# LPDDR4_4X.net
KiCad netlist of a schematic drawn in Altium Designer
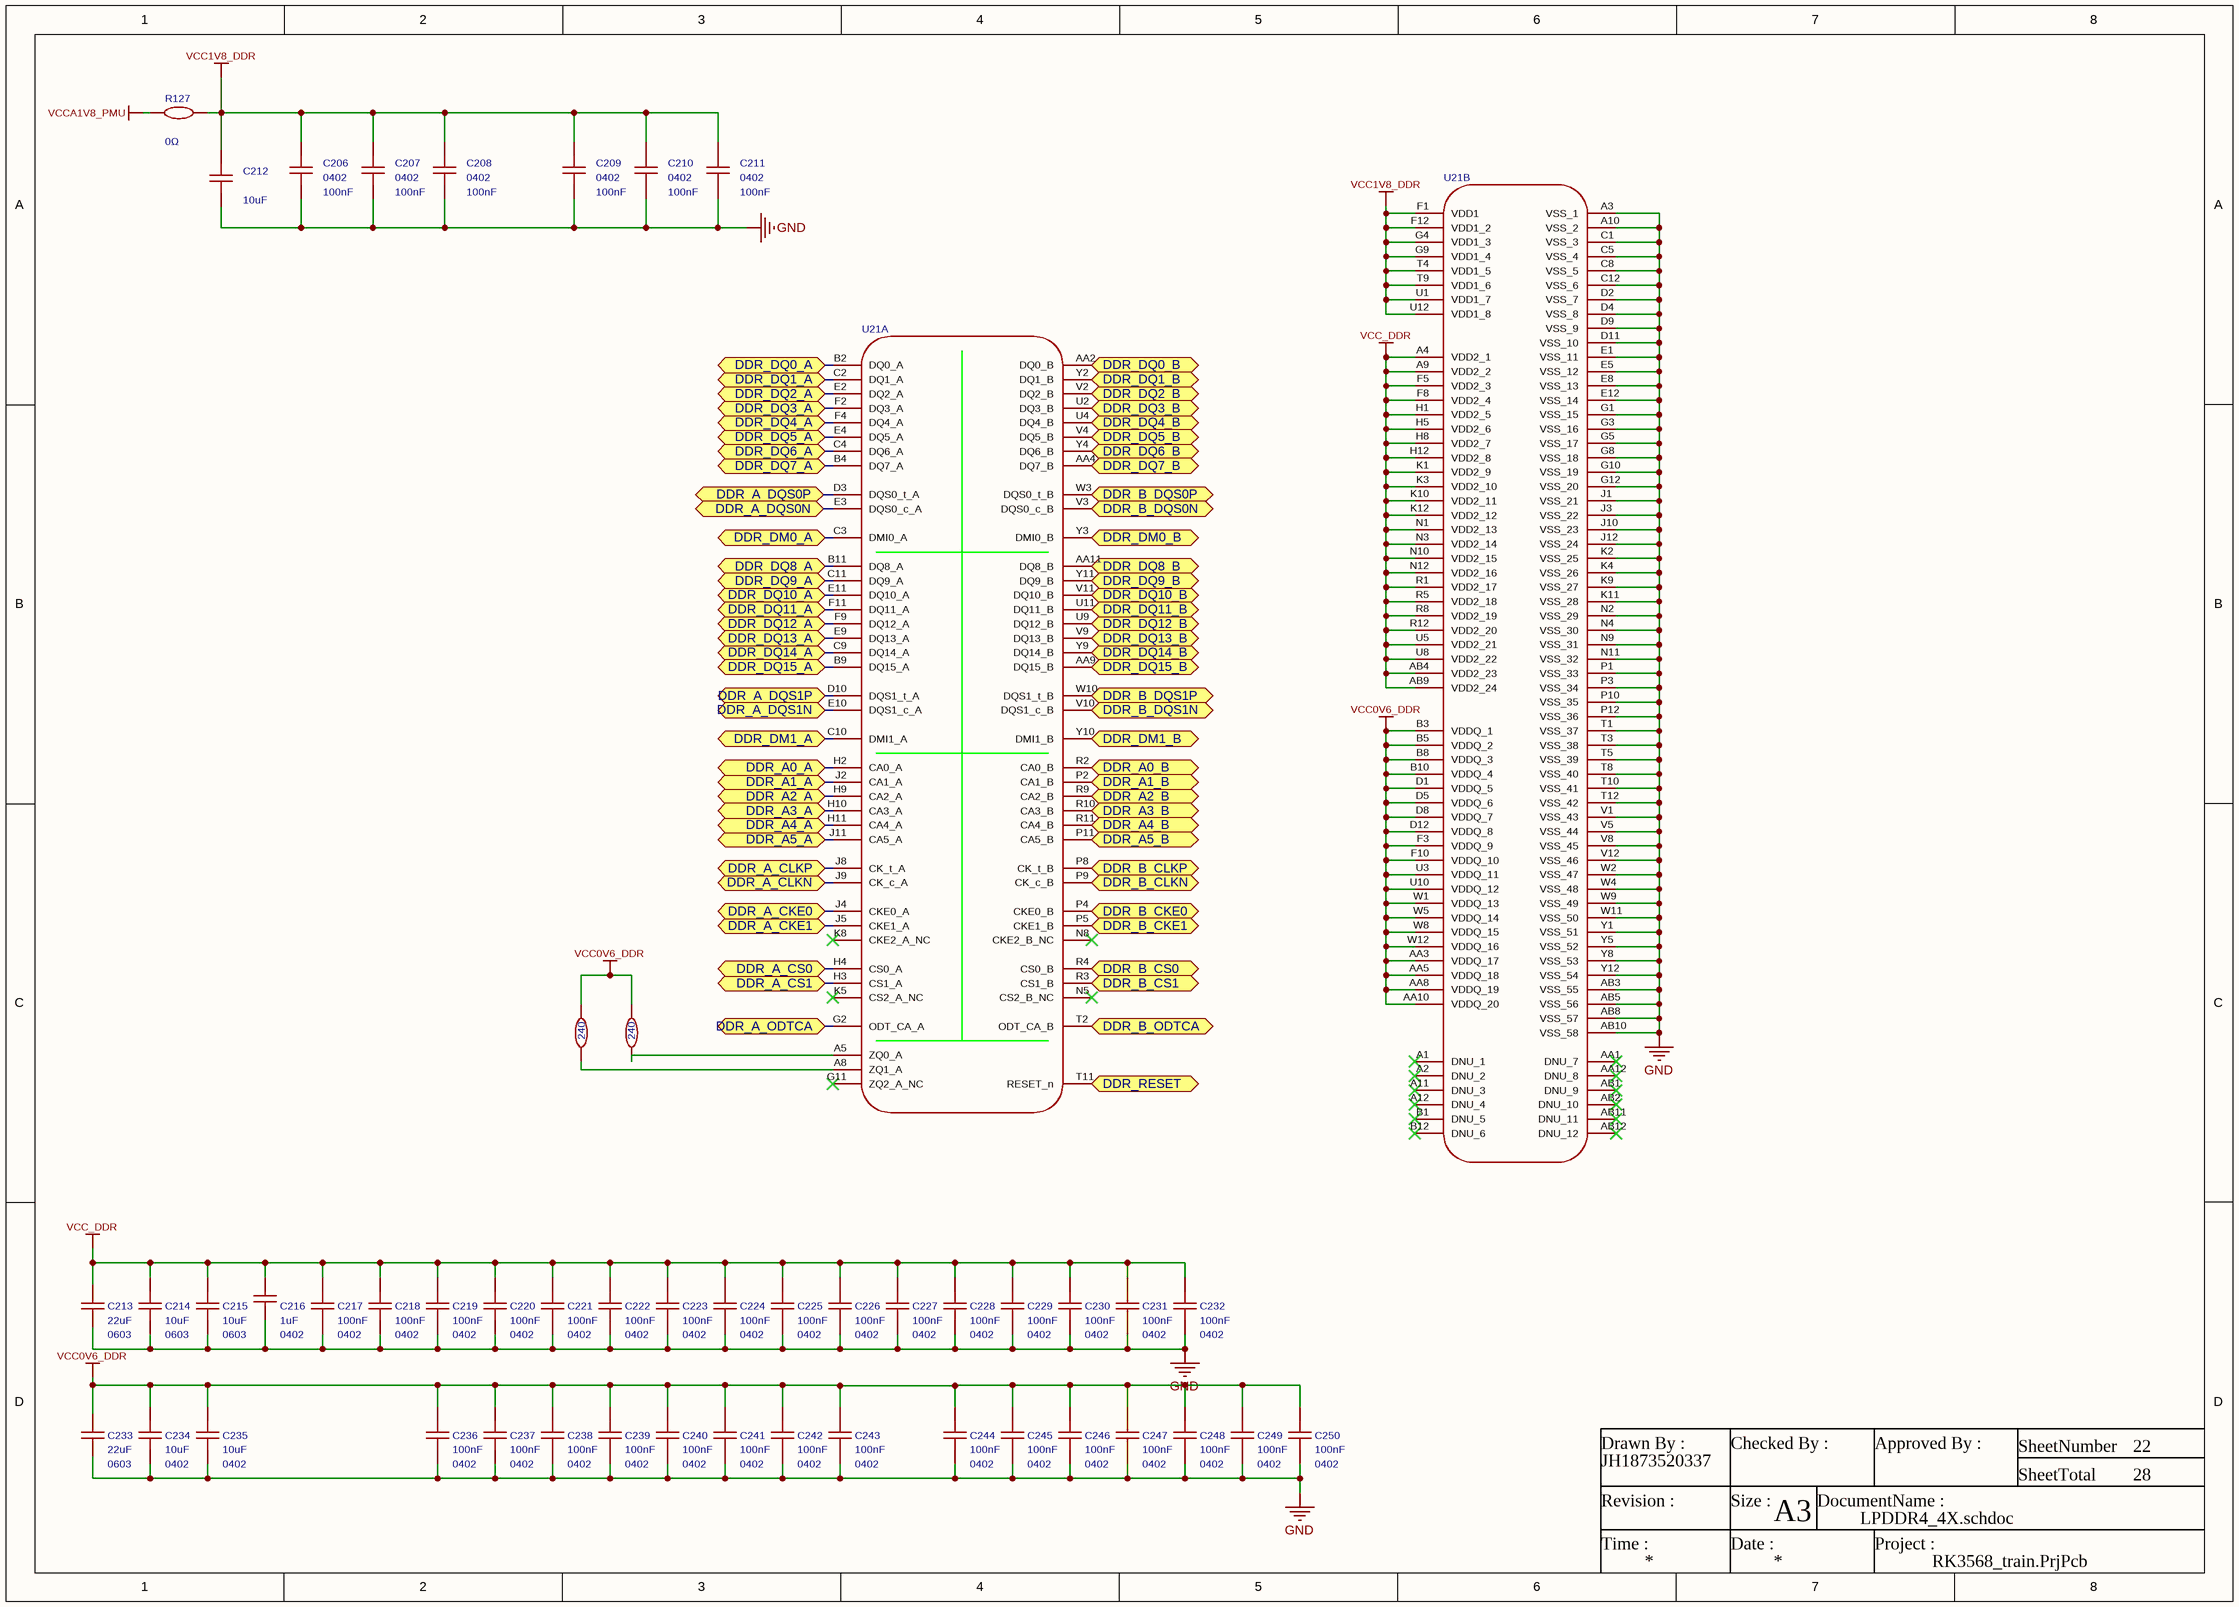
[diagram p0: LPDDR4_4X.schdoc]

(export (version "E")
  (design (tool "Eeschema 10.0.6"))
  (components
    (comp (ref "C206")
      (value "100nF")
      (footprint "MYC0402")
      (description "容值:100nF;精度:±10%;额定电压:50V;材质(温度系数):X7R;")
      (fields
        (field (name "SUPPLIER FOOTPRINT") "0402")
        (field (name "MANUFACTURER") "SAMSUNG(三星)")
        (field (name "MANUFACTURERPART") "CL05B104KB54PNC")
      )
      (libsource (lib "altium-import") (part "root_0_CL05B104KB54PNC_"))
    )
    (comp (ref "C207")
      (value "100nF")
      (footprint "MYC0402")
      (description "容值:100nF;精度:±10%;额定电压:50V;材质(温度系数):X7R;")
      (fields
        (field (name "SUPPLIER FOOTPRINT") "0402")
        (field (name "MANUFACTURER") "SAMSUNG(三星)")
        (field (name "MANUFACTURERPART") "CL05B104KB54PNC")
      )
      (libsource (lib "altium-import") (part "root_0_CL05B104KB54PNC_"))
    )
    (comp (ref "C208")
      (value "100nF")
      (footprint "MYC0402")
      (description "容值:100nF;精度:±10%;额定电压:50V;材质(温度系数):X7R;")
      (fields
        (field (name "SUPPLIER FOOTPRINT") "0402")
        (field (name "MANUFACTURER") "SAMSUNG(三星)")
        (field (name "MANUFACTURERPART") "CL05B104KB54PNC")
      )
      (libsource (lib "altium-import") (part "root_0_CL05B104KB54PNC_"))
    )
    (comp (ref "C209")
      (value "100nF")
      (footprint "MYC0402")
      (description "容值:100nF;精度:±10%;额定电压:50V;材质(温度系数):X7R;")
      (fields
        (field (name "SUPPLIER FOOTPRINT") "0402")
        (field (name "MANUFACTURER") "SAMSUNG(三星)")
        (field (name "MANUFACTURERPART") "CL05B104KB54PNC")
      )
      (libsource (lib "altium-import") (part "root_0_CL05B104KB54PNC_"))
    )
    (comp (ref "C210")
      (value "100nF")
      (footprint "MYC0402")
      (description "容值:100nF;精度:±10%;额定电压:50V;材质(温度系数):X7R;")
      (fields
        (field (name "SUPPLIER FOOTPRINT") "0402")
        (field (name "MANUFACTURER") "SAMSUNG(三星)")
        (field (name "MANUFACTURERPART") "CL05B104KB54PNC")
      )
      (libsource (lib "altium-import") (part "root_0_CL05B104KB54PNC_"))
    )
    (comp (ref "C211")
      (value "100nF")
      (footprint "MYC0402")
      (description "容值:100nF;精度:±10%;额定电压:50V;材质(温度系数):X7R;")
      (fields
        (field (name "SUPPLIER FOOTPRINT") "0402")
        (field (name "MANUFACTURER") "SAMSUNG(三星)")
        (field (name "MANUFACTURERPART") "CL05B104KB54PNC")
      )
      (libsource (lib "altium-import") (part "root_0_CL05B104KB54PNC_"))
    )
    (comp (ref "C212")
      (value "10uF")
      (footprint "C0603")
      (description "容值:10uF;精度:±10%;额定电压:10V;材质(温度系数):X5R;")
      (fields (field (name "MANUFACTURER") "SAMSUNG(三星)") (field (name "MANUFACTURERPART") "CL10A106KP8NNNC"))
      (libsource (lib "altium-import") (part "root_1_CL10A106KP8NNNC_"))
    )
    (comp (ref "C213")
      (value "22uF")
      (footprint "C0603")
      (description "容值:22uF;精度:±20%;额定电压:6.3V;材质(温度系数):X5R;")
      (fields
        (field (name "SUPPLIER FOOTPRINT") "0603")
        (field (name "MANUFACTURER") "SAMSUNG(三星)")
        (field (name "MANUFACTURERPART") "CL10A226MQ8NRNC")
      )
      (libsource (lib "altium-import") (part "root_1_CL10A226MQ8NRNC_"))
    )
    (comp (ref "C214")
      (value "10uF")
      (footprint "C0603")
      (description "容值:10uF;精度:±10%;额定电压:10V;材质(温度系数):X5R;")
      (fields
        (field (name "SUPPLIER FOOTPRINT") "0603")
        (field (name "MANUFACTURER") "SAMSUNG(三星)")
        (field (name "MANUFACTURERPART") "CL10A106KP8NNNC")
      )
      (libsource (lib "altium-import") (part "root_1_CL10A106KP8NNNC_"))
    )
    (comp (ref "C215")
      (value "10uF")
      (footprint "C0603")
      (description "容值:10uF;精度:±10%;额定电压:10V;材质(温度系数):X5R;")
      (fields
        (field (name "SUPPLIER FOOTPRINT") "0603")
        (field (name "MANUFACTURER") "SAMSUNG(三星)")
        (field (name "MANUFACTURERPART") "CL10A106KP8NNNC")
      )
      (libsource (lib "altium-import") (part "root_1_CL10A106KP8NNNC_"))
    )
    (comp (ref "C216")
      (value "1uF")
      (footprint "MYC0402")
      (description "容值:1uF;精度:±10%;额定电压:10V;材质(温度系数):X5R;")
      (fields
        (field (name "SUPPLIER FOOTPRINT") "0402")
        (field (name "MANUFACTURER") "SAMSUNG(三星)")
        (field (name "MANUFACTURERPART") "CL05A105KP5NNNC")
      )
      (libsource (lib "altium-import") (part "root_1_CL05A105KP5NNNC_"))
    )
    (comp (ref "C217")
      (value "100nF")
      (footprint "MYC0402")
      (description "容值:100nF;精度:±10%;额定电压:50V;材质(温度系数):X7R;")
      (fields
        (field (name "SUPPLIER FOOTPRINT") "0402")
        (field (name "MANUFACTURER") "SAMSUNG(三星)")
        (field (name "MANUFACTURERPART") "CL05B104KB54PNC")
      )
      (libsource (lib "altium-import") (part "root_2_CL05B104KB54PNC_"))
    )
    (comp (ref "C218")
      (value "100nF")
      (footprint "MYC0402")
      (description "容值:100nF;精度:±10%;额定电压:50V;材质(温度系数):X7R;")
      (fields
        (field (name "SUPPLIER FOOTPRINT") "0402")
        (field (name "MANUFACTURER") "SAMSUNG(三星)")
        (field (name "MANUFACTURERPART") "CL05B104KB54PNC")
      )
      (libsource (lib "altium-import") (part "root_2_CL05B104KB54PNC_"))
    )
    (comp (ref "C219")
      (value "100nF")
      (footprint "MYC0402")
      (description "容值:100nF;精度:±10%;额定电压:50V;材质(温度系数):X7R;")
      (fields
        (field (name "SUPPLIER FOOTPRINT") "0402")
        (field (name "MANUFACTURER") "SAMSUNG(三星)")
        (field (name "MANUFACTURERPART") "CL05B104KB54PNC")
      )
      (libsource (lib "altium-import") (part "root_2_CL05B104KB54PNC_"))
    )
    (comp (ref "C220")
      (value "100nF")
      (footprint "MYC0402")
      (description "容值:100nF;精度:±10%;额定电压:50V;材质(温度系数):X7R;")
      (fields
        (field (name "SUPPLIER FOOTPRINT") "0402")
        (field (name "MANUFACTURER") "SAMSUNG(三星)")
        (field (name "MANUFACTURERPART") "CL05B104KB54PNC")
      )
      (libsource (lib "altium-import") (part "root_2_CL05B104KB54PNC_"))
    )
    (comp (ref "C221")
      (value "100nF")
      (footprint "MYC0402")
      (description "容值:100nF;精度:±10%;额定电压:50V;材质(温度系数):X7R;")
      (fields
        (field (name "SUPPLIER FOOTPRINT") "0402")
        (field (name "MANUFACTURER") "SAMSUNG(三星)")
        (field (name "MANUFACTURERPART") "CL05B104KB54PNC")
      )
      (libsource (lib "altium-import") (part "root_2_CL05B104KB54PNC_"))
    )
    (comp (ref "C222")
      (value "100nF")
      (footprint "MYC0402")
      (description "容值:100nF;精度:±10%;额定电压:50V;材质(温度系数):X7R;")
      (fields
        (field (name "SUPPLIER FOOTPRINT") "0402")
        (field (name "MANUFACTURER") "SAMSUNG(三星)")
        (field (name "MANUFACTURERPART") "CL05B104KB54PNC")
      )
      (libsource (lib "altium-import") (part "root_2_CL05B104KB54PNC_"))
    )
    (comp (ref "C223")
      (value "100nF")
      (footprint "MYC0402")
      (description "容值:100nF;精度:±10%;额定电压:50V;材质(温度系数):X7R;")
      (fields
        (field (name "SUPPLIER FOOTPRINT") "0402")
        (field (name "MANUFACTURER") "SAMSUNG(三星)")
        (field (name "MANUFACTURERPART") "CL05B104KB54PNC")
      )
      (libsource (lib "altium-import") (part "root_2_CL05B104KB54PNC_"))
    )
    (comp (ref "C224")
      (value "100nF")
      (footprint "MYC0402")
      (description "容值:100nF;精度:±10%;额定电压:50V;材质(温度系数):X7R;")
      (fields
        (field (name "SUPPLIER FOOTPRINT") "0402")
        (field (name "MANUFACTURER") "SAMSUNG(三星)")
        (field (name "MANUFACTURERPART") "CL05B104KB54PNC")
      )
      (libsource (lib "altium-import") (part "root_2_CL05B104KB54PNC_"))
    )
    (comp (ref "C225")
      (value "100nF")
      (footprint "MYC0402")
      (description "容值:100nF;精度:±10%;额定电压:50V;材质(温度系数):X7R;")
      (fields
        (field (name "SUPPLIER FOOTPRINT") "0402")
        (field (name "MANUFACTURER") "SAMSUNG(三星)")
        (field (name "MANUFACTURERPART") "CL05B104KB54PNC")
      )
      (libsource (lib "altium-import") (part "root_2_CL05B104KB54PNC_"))
    )
    (comp (ref "C226")
      (value "100nF")
      (footprint "MYC0402")
      (description "容值:100nF;精度:±10%;额定电压:50V;材质(温度系数):X7R;")
      (fields
        (field (name "SUPPLIER FOOTPRINT") "0402")
        (field (name "MANUFACTURER") "SAMSUNG(三星)")
        (field (name "MANUFACTURERPART") "CL05B104KB54PNC")
      )
      (libsource (lib "altium-import") (part "root_2_CL05B104KB54PNC_"))
    )
    (comp (ref "C227")
      (value "100nF")
      (footprint "MYC0402")
      (description "容值:100nF;精度:±10%;额定电压:50V;材质(温度系数):X7R;")
      (fields
        (field (name "SUPPLIER FOOTPRINT") "0402")
        (field (name "MANUFACTURER") "SAMSUNG(三星)")
        (field (name "MANUFACTURERPART") "CL05B104KB54PNC")
      )
      (libsource (lib "altium-import") (part "root_2_CL05B104KB54PNC_"))
    )
    (comp (ref "C228")
      (value "100nF")
      (footprint "MYC0402")
      (description "容值:100nF;精度:±10%;额定电压:50V;材质(温度系数):X7R;")
      (fields
        (field (name "SUPPLIER FOOTPRINT") "0402")
        (field (name "MANUFACTURER") "SAMSUNG(三星)")
        (field (name "MANUFACTURERPART") "CL05B104KB54PNC")
      )
      (libsource (lib "altium-import") (part "root_2_CL05B104KB54PNC_"))
    )
    (comp (ref "C229")
      (value "100nF")
      (footprint "MYC0402")
      (description "容值:100nF;精度:±10%;额定电压:50V;材质(温度系数):X7R;")
      (fields
        (field (name "SUPPLIER FOOTPRINT") "0402")
        (field (name "MANUFACTURER") "SAMSUNG(三星)")
        (field (name "MANUFACTURERPART") "CL05B104KB54PNC")
      )
      (libsource (lib "altium-import") (part "root_2_CL05B104KB54PNC_"))
    )
    (comp (ref "C230")
      (value "100nF")
      (footprint "MYC0402")
      (description "容值:100nF;精度:±10%;额定电压:50V;材质(温度系数):X7R;")
      (fields
        (field (name "SUPPLIER FOOTPRINT") "0402")
        (field (name "MANUFACTURER") "SAMSUNG(三星)")
        (field (name "MANUFACTURERPART") "CL05B104KB54PNC")
      )
      (libsource (lib "altium-import") (part "root_2_CL05B104KB54PNC_"))
    )
    (comp (ref "C231")
      (value "100nF")
      (footprint "MYC0402")
      (description "容值:100nF;精度:±10%;额定电压:50V;材质(温度系数):X7R;")
      (fields
        (field (name "SUPPLIER FOOTPRINT") "0402")
        (field (name "MANUFACTURER") "SAMSUNG(三星)")
        (field (name "MANUFACTURERPART") "CL05B104KB54PNC")
      )
      (libsource (lib "altium-import") (part "root_2_CL05B104KB54PNC_"))
    )
    (comp (ref "C232")
      (value "100nF")
      (footprint "MYC0402")
      (description "容值:100nF;精度:±10%;额定电压:50V;材质(温度系数):X7R;")
      (fields
        (field (name "SUPPLIER FOOTPRINT") "0402")
        (field (name "MANUFACTURER") "SAMSUNG(三星)")
        (field (name "MANUFACTURERPART") "CL05B104KB54PNC")
      )
      (libsource (lib "altium-import") (part "root_2_CL05B104KB54PNC_"))
    )
    (comp (ref "C233")
      (value "22uF")
      (footprint "C0603")
      (description "容值:22uF;精度:±20%;额定电压:6.3V;材质(温度系数):X5R;")
      (fields
        (field (name "SUPPLIER FOOTPRINT") "0603")
        (field (name "MANUFACTURER") "SAMSUNG(三星)")
        (field (name "MANUFACTURERPART") "CL10A226MQ8NRNC")
      )
      (libsource (lib "altium-import") (part "root_1_CL10A226MQ8NRNC_"))
    )
    (comp (ref "C234")
      (value "10uF")
      (footprint "MYC0402")
      (description "容值:10uF;精度:±20%;额定电压:6.3V;材质(温度系数):X5R;")
      (fields
        (field (name "SUPPLIER FOOTPRINT") "0402")
        (field (name "MANUFACTURER") "SAMSUNG(三星)")
        (field (name "MANUFACTURERPART") "CL05A106MQ5NUNC")
      )
      (libsource (lib "altium-import") (part "root_1_CL05A106MQ5NUNC_"))
    )
    (comp (ref "C235")
      (value "10uF")
      (footprint "MYC0402")
      (description "容值:10uF;精度:±20%;额定电压:6.3V;材质(温度系数):X5R;")
      (fields
        (field (name "SUPPLIER FOOTPRINT") "0402")
        (field (name "MANUFACTURER") "SAMSUNG(三星)")
        (field (name "MANUFACTURERPART") "CL05A106MQ5NUNC")
      )
      (libsource (lib "altium-import") (part "root_1_CL05A106MQ5NUNC_"))
    )
    (comp (ref "C236")
      (value "100nF")
      (footprint "MYC0402")
      (description "容值:100nF;精度:±10%;额定电压:50V;材质(温度系数):X7R;")
      (fields
        (field (name "SUPPLIER FOOTPRINT") "0402")
        (field (name "MANUFACTURER") "SAMSUNG(三星)")
        (field (name "MANUFACTURERPART") "CL05B104KB54PNC")
      )
      (libsource (lib "altium-import") (part "root_2_CL05B104KB54PNC_"))
    )
    (comp (ref "C237")
      (value "100nF")
      (footprint "MYC0402")
      (description "容值:100nF;精度:±10%;额定电压:50V;材质(温度系数):X7R;")
      (fields
        (field (name "SUPPLIER FOOTPRINT") "0402")
        (field (name "MANUFACTURER") "SAMSUNG(三星)")
        (field (name "MANUFACTURERPART") "CL05B104KB54PNC")
      )
      (libsource (lib "altium-import") (part "root_2_CL05B104KB54PNC_"))
    )
    (comp (ref "C238")
      (value "100nF")
      (footprint "MYC0402")
      (description "容值:100nF;精度:±10%;额定电压:50V;材质(温度系数):X7R;")
      (fields
        (field (name "SUPPLIER FOOTPRINT") "0402")
        (field (name "MANUFACTURER") "SAMSUNG(三星)")
        (field (name "MANUFACTURERPART") "CL05B104KB54PNC")
      )
      (libsource (lib "altium-import") (part "root_2_CL05B104KB54PNC_"))
    )
    (comp (ref "C239")
      (value "100nF")
      (footprint "MYC0402")
      (description "容值:100nF;精度:±10%;额定电压:50V;材质(温度系数):X7R;")
      (fields
        (field (name "SUPPLIER FOOTPRINT") "0402")
        (field (name "MANUFACTURER") "SAMSUNG(三星)")
        (field (name "MANUFACTURERPART") "CL05B104KB54PNC")
      )
      (libsource (lib "altium-import") (part "root_2_CL05B104KB54PNC_"))
    )
    (comp (ref "C240")
      (value "100nF")
      (footprint "MYC0402")
      (description "容值:100nF;精度:±10%;额定电压:50V;材质(温度系数):X7R;")
      (fields
        (field (name "SUPPLIER FOOTPRINT") "0402")
        (field (name "MANUFACTURER") "SAMSUNG(三星)")
        (field (name "MANUFACTURERPART") "CL05B104KB54PNC")
      )
      (libsource (lib "altium-import") (part "root_2_CL05B104KB54PNC_"))
    )
    (comp (ref "C241")
      (value "100nF")
      (footprint "MYC0402")
      (description "容值:100nF;精度:±10%;额定电压:50V;材质(温度系数):X7R;")
      (fields
        (field (name "SUPPLIER FOOTPRINT") "0402")
        (field (name "MANUFACTURER") "SAMSUNG(三星)")
        (field (name "MANUFACTURERPART") "CL05B104KB54PNC")
      )
      (libsource (lib "altium-import") (part "root_2_CL05B104KB54PNC_"))
    )
    (comp (ref "C242")
      (value "100nF")
      (footprint "MYC0402")
      (description "容值:100nF;精度:±10%;额定电压:50V;材质(温度系数):X7R;")
      (fields
        (field (name "SUPPLIER FOOTPRINT") "0402")
        (field (name "MANUFACTURER") "SAMSUNG(三星)")
        (field (name "MANUFACTURERPART") "CL05B104KB54PNC")
      )
      (libsource (lib "altium-import") (part "root_2_CL05B104KB54PNC_"))
    )
    (comp (ref "C243")
      (value "100nF")
      (footprint "MYC0402")
      (description "容值:100nF;精度:±10%;额定电压:50V;材质(温度系数):X7R;")
      (fields
        (field (name "SUPPLIER FOOTPRINT") "0402")
        (field (name "MANUFACTURER") "SAMSUNG(三星)")
        (field (name "MANUFACTURERPART") "CL05B104KB54PNC")
      )
      (libsource (lib "altium-import") (part "root_2_CL05B104KB54PNC_"))
    )
    (comp (ref "C244")
      (value "100nF")
      (footprint "MYC0402")
      (description "容值:100nF;精度:±10%;额定电压:50V;材质(温度系数):X7R;")
      (fields
        (field (name "SUPPLIER FOOTPRINT") "0402")
        (field (name "MANUFACTURER") "SAMSUNG(三星)")
        (field (name "MANUFACTURERPART") "CL05B104KB54PNC")
      )
      (libsource (lib "altium-import") (part "root_2_CL05B104KB54PNC_"))
    )
    (comp (ref "C245")
      (value "100nF")
      (footprint "MYC0402")
      (description "容值:100nF;精度:±10%;额定电压:50V;材质(温度系数):X7R;")
      (fields
        (field (name "SUPPLIER FOOTPRINT") "0402")
        (field (name "MANUFACTURER") "SAMSUNG(三星)")
        (field (name "MANUFACTURERPART") "CL05B104KB54PNC")
      )
      (libsource (lib "altium-import") (part "root_2_CL05B104KB54PNC_"))
    )
    (comp (ref "C246")
      (value "100nF")
      (footprint "MYC0402")
      (description "容值:100nF;精度:±10%;额定电压:50V;材质(温度系数):X7R;")
      (fields
        (field (name "SUPPLIER FOOTPRINT") "0402")
        (field (name "MANUFACTURER") "SAMSUNG(三星)")
        (field (name "MANUFACTURERPART") "CL05B104KB54PNC")
      )
      (libsource (lib "altium-import") (part "root_2_CL05B104KB54PNC_"))
    )
    (comp (ref "C247")
      (value "100nF")
      (footprint "MYC0402")
      (description "容值:100nF;精度:±10%;额定电压:50V;材质(温度系数):X7R;")
      (fields
        (field (name "SUPPLIER FOOTPRINT") "0402")
        (field (name "MANUFACTURER") "SAMSUNG(三星)")
        (field (name "MANUFACTURERPART") "CL05B104KB54PNC")
      )
      (libsource (lib "altium-import") (part "root_2_CL05B104KB54PNC_"))
    )
    (comp (ref "C248")
      (value "100nF")
      (footprint "MYC0402")
      (description "容值:100nF;精度:±10%;额定电压:50V;材质(温度系数):X7R;")
      (fields
        (field (name "SUPPLIER FOOTPRINT") "0402")
        (field (name "MANUFACTURER") "SAMSUNG(三星)")
        (field (name "MANUFACTURERPART") "CL05B104KB54PNC")
      )
      (libsource (lib "altium-import") (part "root_2_CL05B104KB54PNC_"))
    )
    (comp (ref "C249")
      (value "100nF")
      (footprint "MYC0402")
      (description "容值:100nF;精度:±10%;额定电压:50V;材质(温度系数):X7R;")
      (fields
        (field (name "SUPPLIER FOOTPRINT") "0402")
        (field (name "MANUFACTURER") "SAMSUNG(三星)")
        (field (name "MANUFACTURERPART") "CL05B104KB54PNC")
      )
      (libsource (lib "altium-import") (part "root_2_CL05B104KB54PNC_"))
    )
    (comp (ref "C250")
      (value "100nF")
      (footprint "MYC0402")
      (description "容值:100nF;精度:±10%;额定电压:50V;材质(温度系数):X7R;")
      (fields
        (field (name "SUPPLIER FOOTPRINT") "0402")
        (field (name "MANUFACTURER") "SAMSUNG(三星)")
        (field (name "MANUFACTURERPART") "CL05B104KB54PNC")
      )
      (libsource (lib "altium-import") (part "root_2_CL05B104KB54PNC_"))
    )
    (comp (ref "R127")
      (value "0Ω")
      (footprint "R0603")
      (description "电阻类型:厚膜电阻;阻值:0Ω;精度:±1%;功率:100mW;最大工作电压:75V;工作温度范围:-55℃~+155℃;")
      (fields
        (field (name "MANUFACTURER") "UNI-ROYAL(厚声)")
        (field (name "MANUFACTURERPART") "0603WAF0000T5E")
      )
      (libsource (lib "altium-import") (part "root_2_0603WAF0000T5E_"))
    )
    (comp (ref "R128")
      (value "240")
      (footprint "r0402-nsk")
      (fields (field (name "Comment") "Res_0402"))
      (libsource (lib "altium-import") (part "root_1_Res_0402_"))
    )
    (comp (ref "R129")
      (value "240")
      (footprint "r0402-nsk")
      (fields (field (name "Comment") "Res_0402"))
      (libsource (lib "altium-import") (part "root_1_Res_0402_"))
    )
    (comp (ref "U21")
      (value "LPDDR4")
      (footprint "LPDDR4_MrX")
      (libsource (lib "altium-import") (part "root_0_LPDDR4_"))
    )
  )
  (nets
    (net (code "1") (name "/DDR_A0_A") (class "Default")
      (node (ref "U21") (pin "H2") (pinfunction "CA0_A_H2") (pintype "passive"))
    )
    (net (code "2") (name "/DDR_A0_B") (class "Default")
      (node (ref "U21") (pin "R2") (pinfunction "CA0_B_R2") (pintype "passive"))
    )
    (net (code "3") (name "/DDR_A1_A") (class "Default")
      (node (ref "U21") (pin "J2") (pinfunction "CA1_A_J2") (pintype "passive"))
    )
    (net (code "4") (name "/DDR_A1_B") (class "Default")
      (node (ref "U21") (pin "P2") (pinfunction "CA1_B_P2") (pintype "passive"))
    )
    (net (code "5") (name "/DDR_A2_A") (class "Default")
      (node (ref "U21") (pin "H9") (pinfunction "CA2_A_H9") (pintype "passive"))
    )
    (net (code "6") (name "/DDR_A2_B") (class "Default")
      (node (ref "U21") (pin "R9") (pinfunction "CA2_B_R9") (pintype "passive"))
    )
    (net (code "7") (name "/DDR_A3_A") (class "Default")
      (node (ref "U21") (pin "H10") (pinfunction "CA3_A_H10") (pintype "passive"))
    )
    (net (code "8") (name "/DDR_A3_B") (class "Default")
      (node (ref "U21") (pin "R10") (pinfunction "CA3_B_R10") (pintype "passive"))
    )
    (net (code "9") (name "/DDR_A4_A") (class "Default")
      (node (ref "U21") (pin "H11") (pinfunction "CA4_A_H11") (pintype "passive"))
    )
    (net (code "10") (name "/DDR_A4_B") (class "Default")
      (node (ref "U21") (pin "R11") (pinfunction "CA4_B_R11") (pintype "passive"))
    )
    (net (code "11") (name "/DDR_A5_A") (class "Default")
      (node (ref "U21") (pin "J11") (pinfunction "CA5_A_J11") (pintype "passive"))
    )
    (net (code "12") (name "/DDR_A5_B") (class "Default")
      (node (ref "U21") (pin "P11") (pinfunction "CA5_B_P11") (pintype "passive"))
    )
    (net (code "13") (name "/DDR_A_CKE0") (class "Default")
      (node (ref "U21") (pin "J4") (pinfunction "CKE0_A_J4") (pintype "passive"))
    )
    (net (code "14") (name "/DDR_A_CKE1") (class "Default")
      (node (ref "U21") (pin "J5") (pinfunction "CKE1_A_J5") (pintype "passive"))
    )
    (net (code "15") (name "/DDR_A_CLKN") (class "Default")
      (node (ref "U21") (pin "J9") (pinfunction "CK_c_A_J9") (pintype "passive"))
    )
    (net (code "16") (name "/DDR_A_CLKP") (class "Default")
      (node (ref "U21") (pin "J8") (pinfunction "CK_t_A_J8") (pintype "passive"))
    )
    (net (code "17") (name "/DDR_A_CS0") (class "Default")
      (node (ref "U21") (pin "H4") (pinfunction "CS0_A_H4") (pintype "passive"))
    )
    (net (code "18") (name "/DDR_A_CS1") (class "Default")
      (node (ref "U21") (pin "H3") (pinfunction "CS1_A_H3") (pintype "passive"))
    )
    (net (code "19") (name "/DDR_A_DQS0N") (class "Default")
      (node (ref "U21") (pin "E3") (pinfunction "DQS0_c_A_E3") (pintype "passive"))
    )
    (net (code "20") (name "/DDR_A_DQS0P") (class "Default")
      (node (ref "U21") (pin "D3") (pinfunction "DQS0_t_A_D3") (pintype "passive"))
    )
    (net (code "21") (name "/DDR_A_DQS1N") (class "Default")
      (node (ref "U21") (pin "E10") (pinfunction "DQS1_c_A_E10") (pintype "passive"))
    )
    (net (code "22") (name "/DDR_A_DQS1P") (class "Default")
      (node (ref "U21") (pin "D10") (pinfunction "DQS1_t_A_D10") (pintype "passive"))
    )
    (net (code "23") (name "/DDR_A_ODTCA") (class "Default")
      (node (ref "U21") (pin "G2") (pinfunction "ODT_CA_A_G2") (pintype "passive"))
    )
    (net (code "24") (name "/DDR_B_CKE0") (class "Default")
      (node (ref "U21") (pin "P4") (pinfunction "CKE0_B_P4") (pintype "passive"))
    )
    (net (code "25") (name "/DDR_B_CKE1") (class "Default")
      (node (ref "U21") (pin "P5") (pinfunction "CKE1_B_P5") (pintype "passive"))
    )
    (net (code "26") (name "/DDR_B_CLKN") (class "Default")
      (node (ref "U21") (pin "P9") (pinfunction "CK_c_B_P9") (pintype "passive"))
    )
    (net (code "27") (name "/DDR_B_CLKP") (class "Default")
      (node (ref "U21") (pin "P8") (pinfunction "CK_t_B_P8") (pintype "passive"))
    )
    (net (code "28") (name "/DDR_B_CS0") (class "Default")
      (node (ref "U21") (pin "R4") (pinfunction "CS0_B_R4") (pintype "passive"))
    )
    (net (code "29") (name "/DDR_B_CS1") (class "Default")
      (node (ref "U21") (pin "R3") (pinfunction "CS1_B_R3") (pintype "passive"))
    )
    (net (code "30") (name "/DDR_B_DQS0N") (class "Default")
      (node (ref "U21") (pin "V3") (pinfunction "DQS0_c_B_V3") (pintype "passive"))
    )
    (net (code "31") (name "/DDR_B_DQS0P") (class "Default")
      (node (ref "U21") (pin "W3") (pinfunction "DQS0_t_B_W3") (pintype "passive"))
    )
    (net (code "32") (name "/DDR_B_DQS1N") (class "Default")
      (node (ref "U21") (pin "V10") (pinfunction "DQS1_c_B_V10") (pintype "passive"))
    )
    (net (code "33") (name "/DDR_B_DQS1P") (class "Default")
      (node (ref "U21") (pin "W10") (pinfunction "DQS1_t_B_W10") (pintype "passive"))
    )
    (net (code "34") (name "/DDR_B_ODTCA") (class "Default")
      (node (ref "U21") (pin "T2") (pinfunction "ODT_CA_B_T2") (pintype "passive"))
    )
    (net (code "35") (name "/DDR_DM0_A") (class "Default")
      (node (ref "U21") (pin "C3") (pinfunction "DMI0_A_C3") (pintype "passive"))
    )
    (net (code "36") (name "/DDR_DM0_B") (class "Default")
      (node (ref "U21") (pin "Y3") (pinfunction "DMI0_B_Y3") (pintype "passive"))
    )
    (net (code "37") (name "/DDR_DM1_A") (class "Default")
      (node (ref "U21") (pin "C10") (pinfunction "DMI1_A_C10") (pintype "passive"))
    )
    (net (code "38") (name "/DDR_DM1_B") (class "Default")
      (node (ref "U21") (pin "Y10") (pinfunction "DMI1_B_Y10") (pintype "passive"))
    )
    (net (code "39") (name "/DDR_DQ0_A") (class "Default")
      (node (ref "U21") (pin "B2") (pinfunction "DQ0_A_B2") (pintype "passive"))
    )
    (net (code "40") (name "/DDR_DQ0_B") (class "Default")
      (node (ref "U21") (pin "AA2") (pinfunction "DQ0_B_AA2") (pintype "passive"))
    )
    (net (code "41") (name "/DDR_DQ1_A") (class "Default")
      (node (ref "U21") (pin "C2") (pinfunction "DQ1_A_C2") (pintype "passive"))
    )
    (net (code "42") (name "/DDR_DQ1_B") (class "Default")
      (node (ref "U21") (pin "Y2") (pinfunction "DQ1_B_Y2") (pintype "passive"))
    )
    (net (code "43") (name "/DDR_DQ2_A") (class "Default")
      (node (ref "U21") (pin "E2") (pinfunction "DQ2_A_E2") (pintype "passive"))
    )
    (net (code "44") (name "/DDR_DQ2_B") (class "Default")
      (node (ref "U21") (pin "V2") (pinfunction "DQ2_B_V2") (pintype "passive"))
    )
    (net (code "45") (name "/DDR_DQ3_A") (class "Default")
      (node (ref "U21") (pin "F2") (pinfunction "DQ3_A_F2") (pintype "passive"))
    )
    (net (code "46") (name "/DDR_DQ3_B") (class "Default")
      (node (ref "U21") (pin "U2") (pinfunction "DQ3_B_U2") (pintype "passive"))
    )
    (net (code "47") (name "/DDR_DQ4_A") (class "Default")
      (node (ref "U21") (pin "F4") (pinfunction "DQ4_A_F4") (pintype "passive"))
    )
    (net (code "48") (name "/DDR_DQ4_B") (class "Default")
      (node (ref "U21") (pin "U4") (pinfunction "DQ4_B_U4") (pintype "passive"))
    )
    (net (code "49") (name "/DDR_DQ5_A") (class "Default")
      (node (ref "U21") (pin "E4") (pinfunction "DQ5_A_E4") (pintype "passive"))
    )
    (net (code "50") (name "/DDR_DQ5_B") (class "Default")
      (node (ref "U21") (pin "V4") (pinfunction "DQ5_B_V4") (pintype "passive"))
    )
    (net (code "51") (name "/DDR_DQ6_A") (class "Default")
      (node (ref "U21") (pin "C4") (pinfunction "DQ6_A_C4") (pintype "passive"))
    )
    (net (code "52") (name "/DDR_DQ6_B") (class "Default")
      (node (ref "U21") (pin "Y4") (pinfunction "DQ6_B_Y4") (pintype "passive"))
    )
    (net (code "53") (name "/DDR_DQ7_A") (class "Default")
      (node (ref "U21") (pin "B4") (pinfunction "DQ7_A_B4") (pintype "passive"))
    )
    (net (code "54") (name "/DDR_DQ7_B") (class "Default")
      (node (ref "U21") (pin "AA4") (pinfunction "DQ7_B_AA4") (pintype "passive"))
    )
    (net (code "55") (name "/DDR_DQ8_A") (class "Default")
      (node (ref "U21") (pin "B11") (pinfunction "DQ8_A_B11") (pintype "passive"))
    )
    (net (code "56") (name "/DDR_DQ8_B") (class "Default")
      (node (ref "U21") (pin "AA11") (pinfunction "DQ8_B_AA11") (pintype "passive"))
    )
    (net (code "57") (name "/DDR_DQ9_A") (class "Default")
      (node (ref "U21") (pin "C11") (pinfunction "DQ9_A_C11") (pintype "passive"))
    )
    (net (code "58") (name "/DDR_DQ9_B") (class "Default")
      (node (ref "U21") (pin "Y11") (pinfunction "DQ9_B_Y11") (pintype "passive"))
    )
    (net (code "59") (name "/DDR_DQ10_A") (class "Default")
      (node (ref "U21") (pin "E11") (pinfunction "DQ10_A_E11") (pintype "passive"))
    )
    (net (code "60") (name "/DDR_DQ10_B") (class "Default")
      (node (ref "U21") (pin "V11") (pinfunction "DQ10_B_V11") (pintype "passive"))
    )
    (net (code "61") (name "/DDR_DQ11_A") (class "Default")
      (node (ref "U21") (pin "F11") (pinfunction "DQ11_A_F11") (pintype "passive"))
    )
    (net (code "62") (name "/DDR_DQ11_B") (class "Default")
      (node (ref "U21") (pin "U11") (pinfunction "DQ11_B_U11") (pintype "passive"))
    )
    (net (code "63") (name "/DDR_DQ12_A") (class "Default")
      (node (ref "U21") (pin "F9") (pinfunction "DQ12_A_F9") (pintype "passive"))
    )
    (net (code "64") (name "/DDR_DQ12_B") (class "Default")
      (node (ref "U21") (pin "U9") (pinfunction "DQ12_B_U9") (pintype "passive"))
    )
    (net (code "65") (name "/DDR_DQ13_A") (class "Default")
      (node (ref "U21") (pin "E9") (pinfunction "DQ13_A_E9") (pintype "passive"))
    )
    (net (code "66") (name "/DDR_DQ13_B") (class "Default")
      (node (ref "U21") (pin "V9") (pinfunction "DQ13_B_V9") (pintype "passive"))
    )
    (net (code "67") (name "/DDR_DQ14_A") (class "Default")
      (node (ref "U21") (pin "C9") (pinfunction "DQ14_A_C9") (pintype "passive"))
    )
    (net (code "68") (name "/DDR_DQ14_B") (class "Default")
      (node (ref "U21") (pin "Y9") (pinfunction "DQ14_B_Y9") (pintype "passive"))
    )
    (net (code "69") (name "/DDR_DQ15_A") (class "Default")
      (node (ref "U21") (pin "B9") (pinfunction "DQ15_A_B9") (pintype "passive"))
    )
    (net (code "70") (name "/DDR_DQ15_B") (class "Default")
      (node (ref "U21") (pin "AA9") (pinfunction "DQ15_B_AA9") (pintype "passive"))
    )
    (net (code "71") (name "/DDR_RESET") (class "Default")
      (node (ref "U21") (pin "T11") (pinfunction "RESET_n_T11") (pintype "passive"))
    )
    (net (code "72") (name "GND") (class "Default")
      (node (ref "C206") (pin "1") (pinfunction "1_1") (pintype "passive"))
      (node (ref "C207") (pin "1") (pinfunction "1_1") (pintype "passive"))
      (node (ref "C208") (pin "1") (pinfunction "1_1") (pintype "passive"))
      (node (ref "C209") (pin "1") (pinfunction "1_1") (pintype "passive"))
      (node (ref "C210") (pin "1") (pinfunction "1_1") (pintype "passive"))
      (node (ref "C211") (pin "1") (pinfunction "1_1") (pintype "passive"))
      (node (ref "C212") (pin "1") (pinfunction "1_1") (pintype "passive"))
      (node (ref "C213") (pin "1") (pinfunction "1_1") (pintype "passive"))
      (node (ref "C214") (pin "1") (pinfunction "1_1") (pintype "passive"))
      (node (ref "C215") (pin "1") (pinfunction "1_1") (pintype "passive"))
      (node (ref "C216") (pin "1") (pinfunction "1_1") (pintype "passive"))
      (node (ref "C217") (pin "2") (pinfunction "2_2") (pintype "passive"))
      (node (ref "C218") (pin "2") (pinfunction "2_2") (pintype "passive"))
      (node (ref "C219") (pin "2") (pinfunction "2_2") (pintype "passive"))
      (node (ref "C220") (pin "2") (pinfunction "2_2") (pintype "passive"))
      (node (ref "C221") (pin "2") (pinfunction "2_2") (pintype "passive"))
      (node (ref "C222") (pin "2") (pinfunction "2_2") (pintype "passive"))
      (node (ref "C223") (pin "2") (pinfunction "2_2") (pintype "passive"))
      (node (ref "C224") (pin "2") (pinfunction "2_2") (pintype "passive"))
      (node (ref "C225") (pin "2") (pinfunction "2_2") (pintype "passive"))
      (node (ref "C226") (pin "2") (pinfunction "2_2") (pintype "passive"))
      (node (ref "C227") (pin "2") (pinfunction "2_2") (pintype "passive"))
      (node (ref "C228") (pin "2") (pinfunction "2_2") (pintype "passive"))
      (node (ref "C229") (pin "2") (pinfunction "2_2") (pintype "passive"))
      (node (ref "C230") (pin "2") (pinfunction "2_2") (pintype "passive"))
      (node (ref "C231") (pin "2") (pinfunction "2_2") (pintype "passive"))
      (node (ref "C232") (pin "2") (pinfunction "2_2") (pintype "passive"))
      (node (ref "C233") (pin "1") (pinfunction "1_1") (pintype "passive"))
      (node (ref "C234") (pin "1") (pinfunction "1_1") (pintype "passive"))
      (node (ref "C235") (pin "1") (pinfunction "1_1") (pintype "passive"))
      (node (ref "C236") (pin "2") (pinfunction "2_2") (pintype "passive"))
      (node (ref "C237") (pin "2") (pinfunction "2_2") (pintype "passive"))
      (node (ref "C238") (pin "2") (pinfunction "2_2") (pintype "passive"))
      (node (ref "C239") (pin "2") (pinfunction "2_2") (pintype "passive"))
      (node (ref "C240") (pin "2") (pinfunction "2_2") (pintype "passive"))
      (node (ref "C241") (pin "2") (pinfunction "2_2") (pintype "passive"))
      (node (ref "C242") (pin "2") (pinfunction "2_2") (pintype "passive"))
      (node (ref "C243") (pin "2") (pinfunction "2_2") (pintype "passive"))
      (node (ref "C244") (pin "2") (pinfunction "2_2") (pintype "passive"))
      (node (ref "C245") (pin "2") (pinfunction "2_2") (pintype "passive"))
      (node (ref "C246") (pin "2") (pinfunction "2_2") (pintype "passive"))
      (node (ref "C247") (pin "2") (pinfunction "2_2") (pintype "passive"))
      (node (ref "C248") (pin "2") (pinfunction "2_2") (pintype "passive"))
      (node (ref "C249") (pin "2") (pinfunction "2_2") (pintype "passive"))
      (node (ref "C250") (pin "2") (pinfunction "2_2") (pintype "passive"))
      (node (ref "U21") (pin "A10") (pinfunction "VSS_2_A10") (pintype "passive"))
      (node (ref "U21") (pin "A3") (pinfunction "VSS_1_A3") (pintype "passive"))
      (node (ref "U21") (pin "AB10") (pinfunction "VSS_58_AB10") (pintype "passive"))
      (node (ref "U21") (pin "AB3") (pinfunction "VSS_55_AB3") (pintype "passive"))
      (node (ref "U21") (pin "AB5") (pinfunction "VSS_56_AB5") (pintype "passive"))
      (node (ref "U21") (pin "AB8") (pinfunction "VSS_57_AB8") (pintype "passive"))
      (node (ref "U21") (pin "C1") (pinfunction "VSS_3_C1") (pintype "passive"))
      (node (ref "U21") (pin "C12") (pinfunction "VSS_6_C12") (pintype "passive"))
      (node (ref "U21") (pin "C5") (pinfunction "VSS_4_C5") (pintype "passive"))
      (node (ref "U21") (pin "C8") (pinfunction "VSS_5_C8") (pintype "passive"))
      (node (ref "U21") (pin "D11") (pinfunction "VSS_10_D11") (pintype "passive"))
      (node (ref "U21") (pin "D2") (pinfunction "VSS_7_D2") (pintype "passive"))
      (node (ref "U21") (pin "D4") (pinfunction "VSS_8_D4") (pintype "passive"))
      (node (ref "U21") (pin "D9") (pinfunction "VSS_9_D9") (pintype "passive"))
      (node (ref "U21") (pin "E1") (pinfunction "VSS_11_E1") (pintype "passive"))
      (node (ref "U21") (pin "E12") (pinfunction "VSS_14_E12") (pintype "passive"))
      (node (ref "U21") (pin "E5") (pinfunction "VSS_12_E5") (pintype "passive"))
      (node (ref "U21") (pin "E8") (pinfunction "VSS_13_E8") (pintype "passive"))
      (node (ref "U21") (pin "G1") (pinfunction "VSS_15_G1") (pintype "passive"))
      (node (ref "U21") (pin "G10") (pinfunction "VSS_19_G10") (pintype "passive"))
      (node (ref "U21") (pin "G12") (pinfunction "VSS_20_G12") (pintype "passive"))
      (node (ref "U21") (pin "G3") (pinfunction "VSS_16_G3") (pintype "passive"))
      (node (ref "U21") (pin "G5") (pinfunction "VSS_17_G5") (pintype "passive"))
      (node (ref "U21") (pin "G8") (pinfunction "VSS_18_G8") (pintype "passive"))
      (node (ref "U21") (pin "J1") (pinfunction "VSS_21_J1") (pintype "passive"))
      (node (ref "U21") (pin "J10") (pinfunction "VSS_23_J10") (pintype "passive"))
      (node (ref "U21") (pin "J12") (pinfunction "VSS_24_J12") (pintype "passive"))
      (node (ref "U21") (pin "J3") (pinfunction "VSS_22_J3") (pintype "passive"))
      (node (ref "U21") (pin "K11") (pinfunction "VSS_28_K11") (pintype "passive"))
      (node (ref "U21") (pin "K2") (pinfunction "VSS_25_K2") (pintype "passive"))
      (node (ref "U21") (pin "K4") (pinfunction "VSS_26_K4") (pintype "passive"))
      (node (ref "U21") (pin "K9") (pinfunction "VSS_27_K9") (pintype "passive"))
      (node (ref "U21") (pin "N11") (pinfunction "VSS_32_N11") (pintype "passive"))
      (node (ref "U21") (pin "N2") (pinfunction "VSS_29_N2") (pintype "passive"))
      (node (ref "U21") (pin "N4") (pinfunction "VSS_30_N4") (pintype "passive"))
      (node (ref "U21") (pin "N9") (pinfunction "VSS_31_N9") (pintype "passive"))
      (node (ref "U21") (pin "P1") (pinfunction "VSS_33_P1") (pintype "passive"))
      (node (ref "U21") (pin "P10") (pinfunction "VSS_35_P10") (pintype "passive"))
      (node (ref "U21") (pin "P12") (pinfunction "VSS_36_P12") (pintype "passive"))
      (node (ref "U21") (pin "P3") (pinfunction "VSS_34_P3") (pintype "passive"))
      (node (ref "U21") (pin "T1") (pinfunction "VSS_37_T1") (pintype "passive"))
      (node (ref "U21") (pin "T10") (pinfunction "VSS_41_T10") (pintype "passive"))
      (node (ref "U21") (pin "T12") (pinfunction "VSS_42_T12") (pintype "passive"))
      (node (ref "U21") (pin "T3") (pinfunction "VSS_38_T3") (pintype "passive"))
      (node (ref "U21") (pin "T5") (pinfunction "VSS_39_T5") (pintype "passive"))
      (node (ref "U21") (pin "T8") (pinfunction "VSS_40_T8") (pintype "passive"))
      (node (ref "U21") (pin "V1") (pinfunction "VSS_43_V1") (pintype "passive"))
      (node (ref "U21") (pin "V12") (pinfunction "VSS_46_V12") (pintype "passive"))
      (node (ref "U21") (pin "V5") (pinfunction "VSS_44_V5") (pintype "passive"))
      (node (ref "U21") (pin "V8") (pinfunction "VSS_45_V8") (pintype "passive"))
      (node (ref "U21") (pin "W11") (pinfunction "VSS_50_W11") (pintype "passive"))
      (node (ref "U21") (pin "W2") (pinfunction "VSS_47_W2") (pintype "passive"))
      (node (ref "U21") (pin "W4") (pinfunction "VSS_48_W4") (pintype "passive"))
      (node (ref "U21") (pin "W9") (pinfunction "VSS_49_W9") (pintype "passive"))
      (node (ref "U21") (pin "Y1") (pinfunction "VSS_51_Y1") (pintype "passive"))
      (node (ref "U21") (pin "Y12") (pinfunction "VSS_54_Y12") (pintype "passive"))
      (node (ref "U21") (pin "Y5") (pinfunction "VSS_52_Y5") (pintype "passive"))
      (node (ref "U21") (pin "Y8") (pinfunction "VSS_53_Y8") (pintype "passive"))
    )
    (net (code "73") (name "Net-(U21A-ZQ0_A)") (class "Default")
      (node (ref "R129") (pin "1") (pinfunction "1_1") (pintype "passive"))
      (node (ref "U21") (pin "A5") (pinfunction "ZQ0_A_A5") (pintype "passive"))
    )
    (net (code "74") (name "Net-(U21A-ZQ1_A)") (class "Default")
      (node (ref "R128") (pin "1") (pinfunction "1_1") (pintype "passive"))
      (node (ref "U21") (pin "A8") (pinfunction "ZQ1_A_A8") (pintype "passive"))
    )
    (net (code "75") (name "VCC0V6_DDR") (class "Default")
      (node (ref "C233") (pin "2") (pinfunction "2_2") (pintype "passive"))
      (node (ref "C234") (pin "2") (pinfunction "2_2") (pintype "passive"))
      (node (ref "C235") (pin "2") (pinfunction "2_2") (pintype "passive"))
      (node (ref "C236") (pin "1") (pinfunction "1_1") (pintype "passive"))
      (node (ref "C237") (pin "1") (pinfunction "1_1") (pintype "passive"))
      (node (ref "C238") (pin "1") (pinfunction "1_1") (pintype "passive"))
      (node (ref "C239") (pin "1") (pinfunction "1_1") (pintype "passive"))
      (node (ref "C240") (pin "1") (pinfunction "1_1") (pintype "passive"))
      (node (ref "C241") (pin "1") (pinfunction "1_1") (pintype "passive"))
      (node (ref "C242") (pin "1") (pinfunction "1_1") (pintype "passive"))
      (node (ref "C243") (pin "1") (pinfunction "1_1") (pintype "passive"))
      (node (ref "C244") (pin "1") (pinfunction "1_1") (pintype "passive"))
      (node (ref "C245") (pin "1") (pinfunction "1_1") (pintype "passive"))
      (node (ref "C246") (pin "1") (pinfunction "1_1") (pintype "passive"))
      (node (ref "C247") (pin "1") (pinfunction "1_1") (pintype "passive"))
      (node (ref "C248") (pin "1") (pinfunction "1_1") (pintype "passive"))
      (node (ref "C249") (pin "1") (pinfunction "1_1") (pintype "passive"))
      (node (ref "C250") (pin "1") (pinfunction "1_1") (pintype "passive"))
      (node (ref "R128") (pin "2") (pinfunction "2_2") (pintype "passive"))
      (node (ref "R129") (pin "2") (pinfunction "2_2") (pintype "passive"))
      (node (ref "U21") (pin "AA10") (pinfunction "VDDQ_20_AA10") (pintype "passive"))
      (node (ref "U21") (pin "AA3") (pinfunction "VDDQ_17_AA3") (pintype "passive"))
      (node (ref "U21") (pin "AA5") (pinfunction "VDDQ_18_AA5") (pintype "passive"))
      (node (ref "U21") (pin "AA8") (pinfunction "VDDQ_19_AA8") (pintype "passive"))
      (node (ref "U21") (pin "B10") (pinfunction "VDDQ_4_B10") (pintype "passive"))
      (node (ref "U21") (pin "B3") (pinfunction "VDDQ_1_B3") (pintype "passive"))
      (node (ref "U21") (pin "B5") (pinfunction "VDDQ_2_B5") (pintype "passive"))
      (node (ref "U21") (pin "B8") (pinfunction "VDDQ_3_B8") (pintype "passive"))
      (node (ref "U21") (pin "D1") (pinfunction "VDDQ_5_D1") (pintype "passive"))
      (node (ref "U21") (pin "D12") (pinfunction "VDDQ_8_D12") (pintype "passive"))
      (node (ref "U21") (pin "D5") (pinfunction "VDDQ_6_D5") (pintype "passive"))
      (node (ref "U21") (pin "D8") (pinfunction "VDDQ_7_D8") (pintype "passive"))
      (node (ref "U21") (pin "F10") (pinfunction "VDDQ_10_F10") (pintype "passive"))
      (node (ref "U21") (pin "F3") (pinfunction "VDDQ_9_F3") (pintype "passive"))
      (node (ref "U21") (pin "U10") (pinfunction "VDDQ_12_U10") (pintype "passive"))
      (node (ref "U21") (pin "U3") (pinfunction "VDDQ_11_U3") (pintype "passive"))
      (node (ref "U21") (pin "W1") (pinfunction "VDDQ_13_W1") (pintype "passive"))
      (node (ref "U21") (pin "W12") (pinfunction "VDDQ_16_W12") (pintype "passive"))
      (node (ref "U21") (pin "W5") (pinfunction "VDDQ_14_W5") (pintype "passive"))
      (node (ref "U21") (pin "W8") (pinfunction "VDDQ_15_W8") (pintype "passive"))
    )
    (net (code "76") (name "VCC1V8_DDR") (class "Default")
      (node (ref "C206") (pin "2") (pinfunction "2_2") (pintype "passive"))
      (node (ref "C207") (pin "2") (pinfunction "2_2") (pintype "passive"))
      (node (ref "C208") (pin "2") (pinfunction "2_2") (pintype "passive"))
      (node (ref "C209") (pin "2") (pinfunction "2_2") (pintype "passive"))
      (node (ref "C210") (pin "2") (pinfunction "2_2") (pintype "passive"))
      (node (ref "C211") (pin "2") (pinfunction "2_2") (pintype "passive"))
      (node (ref "C212") (pin "2") (pinfunction "2_2") (pintype "passive"))
      (node (ref "R127") (pin "1") (pinfunction "1_1") (pintype "passive"))
      (node (ref "U21") (pin "F1") (pinfunction "VDD1_F1") (pintype "passive"))
      (node (ref "U21") (pin "F12") (pinfunction "VDD1_2_F12") (pintype "passive"))
      (node (ref "U21") (pin "G4") (pinfunction "VDD1_3_G4") (pintype "passive"))
      (node (ref "U21") (pin "G9") (pinfunction "VDD1_4_G9") (pintype "passive"))
      (node (ref "U21") (pin "T4") (pinfunction "VDD1_5_T4") (pintype "passive"))
      (node (ref "U21") (pin "T9") (pinfunction "VDD1_6_T9") (pintype "passive"))
      (node (ref "U21") (pin "U1") (pinfunction "VDD1_7_U1") (pintype "passive"))
      (node (ref "U21") (pin "U12") (pinfunction "VDD1_8_U12") (pintype "passive"))
    )
    (net (code "77") (name "VCCA1V8_PMU") (class "Default")
      (node (ref "R127") (pin "2") (pinfunction "2_2") (pintype "passive"))
    )
    (net (code "78") (name "VCC_DDR") (class "Default")
      (node (ref "C213") (pin "2") (pinfunction "2_2") (pintype "passive"))
      (node (ref "C214") (pin "2") (pinfunction "2_2") (pintype "passive"))
      (node (ref "C215") (pin "2") (pinfunction "2_2") (pintype "passive"))
      (node (ref "C216") (pin "2") (pinfunction "2_2") (pintype "passive"))
      (node (ref "C217") (pin "1") (pinfunction "1_1") (pintype "passive"))
      (node (ref "C218") (pin "1") (pinfunction "1_1") (pintype "passive"))
      (node (ref "C219") (pin "1") (pinfunction "1_1") (pintype "passive"))
      (node (ref "C220") (pin "1") (pinfunction "1_1") (pintype "passive"))
      (node (ref "C221") (pin "1") (pinfunction "1_1") (pintype "passive"))
      (node (ref "C222") (pin "1") (pinfunction "1_1") (pintype "passive"))
      (node (ref "C223") (pin "1") (pinfunction "1_1") (pintype "passive"))
      (node (ref "C224") (pin "1") (pinfunction "1_1") (pintype "passive"))
      (node (ref "C225") (pin "1") (pinfunction "1_1") (pintype "passive"))
      (node (ref "C226") (pin "1") (pinfunction "1_1") (pintype "passive"))
      (node (ref "C227") (pin "1") (pinfunction "1_1") (pintype "passive"))
      (node (ref "C228") (pin "1") (pinfunction "1_1") (pintype "passive"))
      (node (ref "C229") (pin "1") (pinfunction "1_1") (pintype "passive"))
      (node (ref "C230") (pin "1") (pinfunction "1_1") (pintype "passive"))
      (node (ref "C231") (pin "1") (pinfunction "1_1") (pintype "passive"))
      (node (ref "C232") (pin "1") (pinfunction "1_1") (pintype "passive"))
      (node (ref "U21") (pin "A4") (pinfunction "VDD2_1_A4") (pintype "passive"))
      (node (ref "U21") (pin "A9") (pinfunction "VDD2_2_A9") (pintype "passive"))
      (node (ref "U21") (pin "AB4") (pinfunction "VDD2_23_AB4") (pintype "passive"))
      (node (ref "U21") (pin "AB9") (pinfunction "VDD2_24_AB9") (pintype "passive"))
      (node (ref "U21") (pin "F5") (pinfunction "VDD2_3_F5") (pintype "passive"))
      (node (ref "U21") (pin "F8") (pinfunction "VDD2_4_F8") (pintype "passive"))
      (node (ref "U21") (pin "H1") (pinfunction "VDD2_5_H1") (pintype "passive"))
      (node (ref "U21") (pin "H12") (pinfunction "VDD2_8_H12") (pintype "passive"))
      (node (ref "U21") (pin "H5") (pinfunction "VDD2_6_H5") (pintype "passive"))
      (node (ref "U21") (pin "H8") (pinfunction "VDD2_7_H8") (pintype "passive"))
      (node (ref "U21") (pin "K1") (pinfunction "VDD2_9_K1") (pintype "passive"))
      (node (ref "U21") (pin "K10") (pinfunction "VDD2_11_K10") (pintype "passive"))
      (node (ref "U21") (pin "K12") (pinfunction "VDD2_12_K12") (pintype "passive"))
      (node (ref "U21") (pin "K3") (pinfunction "VDD2_10_K3") (pintype "passive"))
      (node (ref "U21") (pin "N1") (pinfunction "VDD2_13_N1") (pintype "passive"))
      (node (ref "U21") (pin "N10") (pinfunction "VDD2_15_N10") (pintype "passive"))
      (node (ref "U21") (pin "N12") (pinfunction "VDD2_16_N12") (pintype "passive"))
      (node (ref "U21") (pin "N3") (pinfunction "VDD2_14_N3") (pintype "passive"))
      (node (ref "U21") (pin "R1") (pinfunction "VDD2_17_R1") (pintype "passive"))
      (node (ref "U21") (pin "R12") (pinfunction "VDD2_20_R12") (pintype "passive"))
      (node (ref "U21") (pin "R5") (pinfunction "VDD2_18_R5") (pintype "passive"))
      (node (ref "U21") (pin "R8") (pinfunction "VDD2_19_R8") (pintype "passive"))
      (node (ref "U21") (pin "U5") (pinfunction "VDD2_21_U5") (pintype "passive"))
      (node (ref "U21") (pin "U8") (pinfunction "VDD2_22_U8") (pintype "passive"))
    )
    (net (code "79") (name "unconnected-(U21A-CKE2_A_NC-PadK8)") (class "Default")
      (node (ref "U21") (pin "K8") (pinfunction "CKE2_A_NC_K8") (pintype "passive+no_connect"))
    )
    (net (code "80") (name "unconnected-(U21A-CKE2_B_NC-PadN8)") (class "Default")
      (node (ref "U21") (pin "N8") (pinfunction "CKE2_B_NC_N8") (pintype "passive+no_connect"))
    )
    (net (code "81") (name "unconnected-(U21A-CS2_A_NC-PadK5)") (class "Default")
      (node (ref "U21") (pin "K5") (pinfunction "CS2_A_NC_K5") (pintype "passive+no_connect"))
    )
    (net (code "82") (name "unconnected-(U21A-CS2_B_NC-PadN5)") (class "Default")
      (node (ref "U21") (pin "N5") (pinfunction "CS2_B_NC_N5") (pintype "passive+no_connect"))
    )
    (net (code "83") (name "unconnected-(U21A-ZQ2_A_NC-PadG11)") (class "Default")
      (node (ref "U21") (pin "G11") (pinfunction "ZQ2_A_NC_G11") (pintype "passive+no_connect"))
    )
    (net (code "84") (name "unconnected-(U21B-DNU_1-PadA1)") (class "Default")
      (node (ref "U21") (pin "A1") (pinfunction "DNU_1_A1") (pintype "passive+no_connect"))
    )
    (net (code "85") (name "unconnected-(U21B-DNU_2-PadA2)") (class "Default")
      (node (ref "U21") (pin "A2") (pinfunction "DNU_2_A2") (pintype "passive+no_connect"))
    )
    (net (code "86") (name "unconnected-(U21B-DNU_3-PadA11)") (class "Default")
      (node (ref "U21") (pin "A11") (pinfunction "DNU_3_A11") (pintype "passive+no_connect"))
    )
    (net (code "87") (name "unconnected-(U21B-DNU_4-PadA12)") (class "Default")
      (node (ref "U21") (pin "A12") (pinfunction "DNU_4_A12") (pintype "passive+no_connect"))
    )
    (net (code "88") (name "unconnected-(U21B-DNU_5-PadB1)") (class "Default")
      (node (ref "U21") (pin "B1") (pinfunction "DNU_5_B1") (pintype "passive+no_connect"))
    )
    (net (code "89") (name "unconnected-(U21B-DNU_6-PadB12)") (class "Default")
      (node (ref "U21") (pin "B12") (pinfunction "DNU_6_B12") (pintype "passive+no_connect"))
    )
    (net (code "90") (name "unconnected-(U21B-DNU_7-PadAA1)") (class "Default")
      (node (ref "U21") (pin "AA1") (pinfunction "DNU_7_AA1") (pintype "passive+no_connect"))
    )
    (net (code "91") (name "unconnected-(U21B-DNU_8-PadAA12)") (class "Default")
      (node (ref "U21") (pin "AA12") (pinfunction "DNU_8_AA12") (pintype "passive+no_connect"))
    )
    (net (code "92") (name "unconnected-(U21B-DNU_9-PadAB1)") (class "Default")
      (node (ref "U21") (pin "AB1") (pinfunction "DNU_9_AB1") (pintype "passive+no_connect"))
    )
    (net (code "93") (name "unconnected-(U21B-DNU_10-PadAB2)") (class "Default")
      (node (ref "U21") (pin "AB2") (pinfunction "DNU_10_AB2") (pintype "passive+no_connect"))
    )
    (net (code "94") (name "unconnected-(U21B-DNU_11-PadAB11)") (class "Default")
      (node (ref "U21") (pin "AB11") (pinfunction "DNU_11_AB11") (pintype "passive+no_connect"))
    )
    (net (code "95") (name "unconnected-(U21B-DNU_12-PadAB12)") (class "Default")
      (node (ref "U21") (pin "AB12") (pinfunction "DNU_12_AB12") (pintype "passive+no_connect"))
    )
  )
)
